# Power_Bypass_Caps.net
KiCad netlist of a schematic drawn in Altium Designer
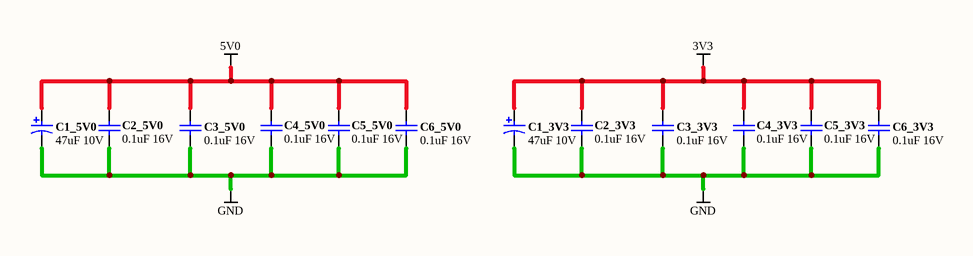
[diagram p0: Power_Bypass_Caps.SchDoc]

(export (version "E")
  (design (tool "Eeschema 10.0.6"))
  (components
    (comp (ref "C1_3V3")
      (value "47uF 10V")
      (footprint "CAPC3528-STAR")
      (description "Capacitor, Tantalum, 47uF 20% 10V MCCT-B (3528-12)")
      (fields (field (name "TOLERANCE") "20 %"))
      (libsource (lib "AltiumDesignLibrary") (part "CAP-P"))
    )
    (comp (ref "C1_5V0")
      (value "47uF 10V")
      (footprint "CAPC3528-STAR")
      (description "Capacitor, Tantalum, 47uF 20% 10V MCCT-B (3528-12)")
      (fields (field (name "TOLERANCE") "20 %"))
      (libsource (lib "AltiumDesignLibrary") (part "CAP-P"))
    )
    (comp (ref "C2_3V3")
      (value "0.1uF 16V")
      (footprint "CAPC1005-STAR")
      (description "Capacitor, Ceramic, 0.1uF 10% 16V 0402 (1005) X7R")
      (fields (field (name "TOLERANCE") "10 %"))
      (libsource (lib "AltiumDesignLibrary") (part "CAP-NP"))
    )
    (comp (ref "C2_5V0")
      (value "0.1uF 16V")
      (footprint "CAPC1005-STAR")
      (description "Capacitor, Ceramic, 0.1uF 10% 16V 0402 (1005) X7R")
      (fields (field (name "TOLERANCE") "10 %"))
      (libsource (lib "AltiumDesignLibrary") (part "CAP-NP"))
    )
    (comp (ref "C3_3V3")
      (value "0.1uF 16V")
      (footprint "CAPC1005-STAR")
      (description "Capacitor, Ceramic, 0.1uF 10% 16V 0402 (1005) X7R")
      (fields (field (name "TOLERANCE") "10 %"))
      (libsource (lib "AltiumDesignLibrary") (part "CAP-NP"))
    )
    (comp (ref "C3_5V0")
      (value "0.1uF 16V")
      (footprint "CAPC1005-STAR")
      (description "Capacitor, Ceramic, 0.1uF 10% 16V 0402 (1005) X7R")
      (fields (field (name "TOLERANCE") "10 %"))
      (libsource (lib "AltiumDesignLibrary") (part "CAP-NP"))
    )
    (comp (ref "C4_3V3")
      (value "0.1uF 16V")
      (footprint "CAPC1005-STAR")
      (description "Capacitor, Ceramic, 0.1uF 10% 16V 0402 (1005) X7R")
      (fields (field (name "TOLERANCE") "10 %"))
      (libsource (lib "AltiumDesignLibrary") (part "CAP-NP"))
    )
    (comp (ref "C4_5V0")
      (value "0.1uF 16V")
      (footprint "CAPC1005-STAR")
      (description "Capacitor, Ceramic, 0.1uF 10% 16V 0402 (1005) X7R")
      (fields (field (name "TOLERANCE") "10 %"))
      (libsource (lib "AltiumDesignLibrary") (part "CAP-NP"))
    )
    (comp (ref "C5_3V3")
      (value "0.1uF 16V")
      (footprint "CAPC1005-STAR")
      (description "Capacitor, Ceramic, 0.1uF 10% 16V 0402 (1005) X7R")
      (fields (field (name "TOLERANCE") "10 %"))
      (libsource (lib "AltiumDesignLibrary") (part "CAP-NP"))
    )
    (comp (ref "C5_5V0")
      (value "0.1uF 16V")
      (footprint "CAPC1005-STAR")
      (description "Capacitor, Ceramic, 0.1uF 10% 16V 0402 (1005) X7R")
      (fields (field (name "TOLERANCE") "10 %"))
      (libsource (lib "AltiumDesignLibrary") (part "CAP-NP"))
    )
    (comp (ref "C6_3V3")
      (value "0.1uF 16V")
      (footprint "CAPC1005-STAR")
      (description "Capacitor, Ceramic, 0.1uF 10% 16V 0402 (1005) X7R")
      (fields (field (name "TOLERANCE") "10 %"))
      (libsource (lib "AltiumDesignLibrary") (part "CAP-NP"))
    )
    (comp (ref "C6_5V0")
      (value "0.1uF 16V")
      (footprint "CAPC1005-STAR")
      (description "Capacitor, Ceramic, 0.1uF 10% 16V 0402 (1005) X7R")
      (fields (field (name "TOLERANCE") "10 %"))
      (libsource (lib "AltiumDesignLibrary") (part "CAP-NP"))
    )
  )
  (nets
    (net (code "1") (name "3V3") (class "Default")
      (node (ref "C1_3V3") (pin "1") (pinfunction "1_1") (pintype "passive"))
      (node (ref "C2_3V3") (pin "2") (pinfunction "2_2") (pintype "passive"))
      (node (ref "C3_3V3") (pin "1") (pinfunction "1_1") (pintype "passive"))
      (node (ref "C4_3V3") (pin "2") (pinfunction "2_2") (pintype "passive"))
      (node (ref "C5_3V3") (pin "2") (pinfunction "2_2") (pintype "passive"))
      (node (ref "C6_3V3") (pin "1") (pinfunction "1_1") (pintype "passive"))
    )
    (net (code "2") (name "5V0") (class "Default")
      (node (ref "C1_5V0") (pin "1") (pinfunction "1_1") (pintype "passive"))
      (node (ref "C2_5V0") (pin "2") (pinfunction "2_2") (pintype "passive"))
      (node (ref "C3_5V0") (pin "1") (pinfunction "1_1") (pintype "passive"))
      (node (ref "C4_5V0") (pin "2") (pinfunction "2_2") (pintype "passive"))
      (node (ref "C5_5V0") (pin "2") (pinfunction "2_2") (pintype "passive"))
      (node (ref "C6_5V0") (pin "1") (pinfunction "1_1") (pintype "passive"))
    )
    (net (code "3") (name "GND") (class "Default")
      (node (ref "C1_3V3") (pin "2") (pinfunction "2_2") (pintype "passive"))
      (node (ref "C1_5V0") (pin "2") (pinfunction "2_2") (pintype "passive"))
      (node (ref "C2_3V3") (pin "1") (pinfunction "1_1") (pintype "passive"))
      (node (ref "C2_5V0") (pin "1") (pinfunction "1_1") (pintype "passive"))
      (node (ref "C3_3V3") (pin "2") (pinfunction "2_2") (pintype "passive"))
      (node (ref "C3_5V0") (pin "2") (pinfunction "2_2") (pintype "passive"))
      (node (ref "C4_3V3") (pin "1") (pinfunction "1_1") (pintype "passive"))
      (node (ref "C4_5V0") (pin "1") (pinfunction "1_1") (pintype "passive"))
      (node (ref "C5_3V3") (pin "1") (pinfunction "1_1") (pintype "passive"))
      (node (ref "C5_5V0") (pin "1") (pinfunction "1_1") (pintype "passive"))
      (node (ref "C6_3V3") (pin "2") (pinfunction "2_2") (pintype "passive"))
      (node (ref "C6_5V0") (pin "2") (pinfunction "2_2") (pintype "passive"))
    )
  )
)
